# Wiznet.net
KiCad netlist of a schematic drawn in Altium Designer
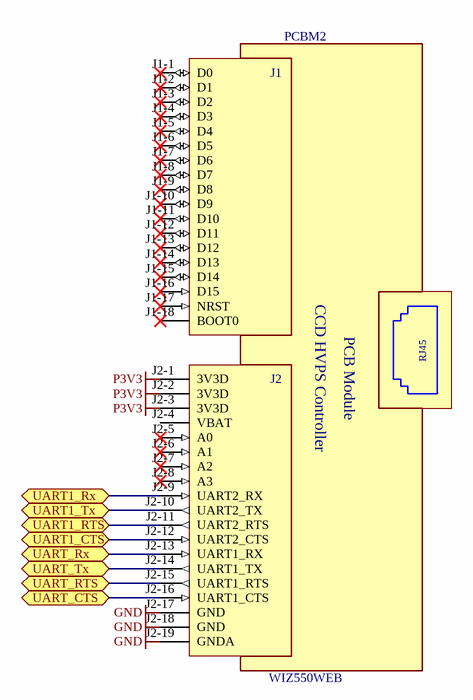
[diagram p0: Wiznet.SchDoc]

(export (version "E")
  (design (tool "Eeschema 10.0.6"))
  (components
    (comp (ref "PCBM2")
      (value "WIZ550WEB")
      (footprint "PCBM_WIZNET_WIZ550WEB")
      (description "Embedded Web Server Module base on W5500 TCP/IP Chip")
      (fields
        (field (name "PART NUMBER") "PCBM_WIZNET_WIZ550WEB")
        (field (name "MANUFACTURER") "WIZNET")
        (field (name "AUTHOR") "CERN DEM MR")
      )
      (libsource (lib "ICs And Semiconductors") (part "PCBM_WIZNET_WIZ550WEB"))
    )
  )
  (nets
    (net (code "1") (name "/UART1_CTS") (class "Default")
      (node (ref "PCBM2") (pin "J2-12") (pinfunction "UART2_CTS_J2-12") (pintype "input"))
    )
    (net (code "2") (name "/UART1_RTS") (class "Default")
      (node (ref "PCBM2") (pin "J2-11") (pinfunction "UART2_RTS_J2-11") (pintype "output"))
    )
    (net (code "3") (name "/UART1_Rx") (class "Default")
      (node (ref "PCBM2") (pin "J2-9") (pinfunction "UART2_RX_J2-9") (pintype "input"))
    )
    (net (code "4") (name "/UART1_Tx") (class "Default")
      (node (ref "PCBM2") (pin "J2-10") (pinfunction "UART2_TX_J2-10") (pintype "output"))
    )
    (net (code "5") (name "/UART_CTS") (class "Default")
      (node (ref "PCBM2") (pin "J2-16") (pinfunction "UART1_CTS_J2-16") (pintype "input"))
    )
    (net (code "6") (name "/UART_RTS") (class "Default")
      (node (ref "PCBM2") (pin "J2-15") (pinfunction "UART1_RTS_J2-15") (pintype "output"))
    )
    (net (code "7") (name "/UART_Rx") (class "Default")
      (node (ref "PCBM2") (pin "J2-13") (pinfunction "UART1_RX_J2-13") (pintype "input"))
    )
    (net (code "8") (name "/UART_Tx") (class "Default")
      (node (ref "PCBM2") (pin "J2-14") (pinfunction "UART1_TX_J2-14") (pintype "output"))
    )
    (net (code "9") (name "GND") (class "Default")
      (node (ref "PCBM2") (pin "J2-17") (pinfunction "GND_J2-17") (pintype "power_in"))
      (node (ref "PCBM2") (pin "J2-18") (pinfunction "GND_J2-18") (pintype "power_in"))
      (node (ref "PCBM2") (pin "J2-19") (pinfunction "GNDA_J2-19") (pintype "power_in"))
    )
    (net (code "10") (name "P3V3") (class "Default")
      (node (ref "PCBM2") (pin "J2-1") (pinfunction "3V3D_J2-1") (pintype "power_in"))
      (node (ref "PCBM2") (pin "J2-2") (pinfunction "3V3D_J2-2") (pintype "power_in"))
      (node (ref "PCBM2") (pin "J2-3") (pinfunction "3V3D_J2-3") (pintype "power_in"))
    )
    (net (code "11") (name "unconnected-(PCBM2-A0-PadJ2-5)") (class "Default")
      (node (ref "PCBM2") (pin "J2-5") (pinfunction "A0_J2-5") (pintype "input+no_connect"))
    )
    (net (code "12") (name "unconnected-(PCBM2-A1-PadJ2-6)") (class "Default")
      (node (ref "PCBM2") (pin "J2-6") (pinfunction "A1_J2-6") (pintype "input+no_connect"))
    )
    (net (code "13") (name "unconnected-(PCBM2-A2-PadJ2-7)") (class "Default")
      (node (ref "PCBM2") (pin "J2-7") (pinfunction "A2_J2-7") (pintype "input+no_connect"))
    )
    (net (code "14") (name "unconnected-(PCBM2-A3-PadJ2-8)") (class "Default")
      (node (ref "PCBM2") (pin "J2-8") (pinfunction "A3_J2-8") (pintype "input+no_connect"))
    )
    (net (code "15") (name "unconnected-(PCBM2-BOOT0-PadJ1-18)") (class "Default")
      (node (ref "PCBM2") (pin "J1-18") (pinfunction "BOOT0_J1-18") (pintype "power_in+no_connect"))
    )
    (net (code "16") (name "unconnected-(PCBM2-D0-PadJ1-1)") (class "Default")
      (node (ref "PCBM2") (pin "J1-1") (pinfunction "D0_J1-1") (pintype "bidirectional+no_connect"))
    )
    (net (code "17") (name "unconnected-(PCBM2-D1-PadJ1-2)") (class "Default")
      (node (ref "PCBM2") (pin "J1-2") (pinfunction "D1_J1-2") (pintype "bidirectional+no_connect"))
    )
    (net (code "18") (name "unconnected-(PCBM2-D2-PadJ1-3)") (class "Default")
      (node (ref "PCBM2") (pin "J1-3") (pinfunction "D2_J1-3") (pintype "bidirectional+no_connect"))
    )
    (net (code "19") (name "unconnected-(PCBM2-D3-PadJ1-4)") (class "Default")
      (node (ref "PCBM2") (pin "J1-4") (pinfunction "D3_J1-4") (pintype "bidirectional+no_connect"))
    )
    (net (code "20") (name "unconnected-(PCBM2-D4-PadJ1-5)") (class "Default")
      (node (ref "PCBM2") (pin "J1-5") (pinfunction "D4_J1-5") (pintype "bidirectional+no_connect"))
    )
    (net (code "21") (name "unconnected-(PCBM2-D5-PadJ1-6)") (class "Default")
      (node (ref "PCBM2") (pin "J1-6") (pinfunction "D5_J1-6") (pintype "bidirectional+no_connect"))
    )
    (net (code "22") (name "unconnected-(PCBM2-D6-PadJ1-7)") (class "Default")
      (node (ref "PCBM2") (pin "J1-7") (pinfunction "D6_J1-7") (pintype "bidirectional+no_connect"))
    )
    (net (code "23") (name "unconnected-(PCBM2-D7-PadJ1-8)") (class "Default")
      (node (ref "PCBM2") (pin "J1-8") (pinfunction "D7_J1-8") (pintype "bidirectional+no_connect"))
    )
    (net (code "24") (name "unconnected-(PCBM2-D8-PadJ1-9)") (class "Default")
      (node (ref "PCBM2") (pin "J1-9") (pinfunction "D8_J1-9") (pintype "bidirectional+no_connect"))
    )
    (net (code "25") (name "unconnected-(PCBM2-D9-PadJ1-10)") (class "Default")
      (node (ref "PCBM2") (pin "J1-10") (pinfunction "D9_J1-10") (pintype "bidirectional+no_connect"))
    )
    (net (code "26") (name "unconnected-(PCBM2-D10-PadJ1-11)") (class "Default")
      (node (ref "PCBM2") (pin "J1-11") (pinfunction "D10_J1-11") (pintype "bidirectional+no_connect"))
    )
    (net (code "27") (name "unconnected-(PCBM2-D11-PadJ1-12)") (class "Default")
      (node (ref "PCBM2") (pin "J1-12") (pinfunction "D11_J1-12") (pintype "bidirectional+no_connect"))
    )
    (net (code "28") (name "unconnected-(PCBM2-D12-PadJ1-13)") (class "Default")
      (node (ref "PCBM2") (pin "J1-13") (pinfunction "D12_J1-13") (pintype "bidirectional+no_connect"))
    )
    (net (code "29") (name "unconnected-(PCBM2-D13-PadJ1-14)") (class "Default")
      (node (ref "PCBM2") (pin "J1-14") (pinfunction "D13_J1-14") (pintype "bidirectional+no_connect"))
    )
    (net (code "30") (name "unconnected-(PCBM2-D14-PadJ1-15)") (class "Default")
      (node (ref "PCBM2") (pin "J1-15") (pinfunction "D14_J1-15") (pintype "bidirectional+no_connect"))
    )
    (net (code "31") (name "unconnected-(PCBM2-D15-PadJ1-16)") (class "Default")
      (node (ref "PCBM2") (pin "J1-16") (pinfunction "D15_J1-16") (pintype "input+no_connect"))
    )
    (net (code "32") (name "unconnected-(PCBM2-NRST-PadJ1-17)") (class "Default")
      (node (ref "PCBM2") (pin "J1-17") (pinfunction "NRST_J1-17") (pintype "input+no_connect"))
    )
    (net (code "33") (name "unconnected-(PCBM2-VBAT-PadJ2-4)") (class "Default")
      (node (ref "PCBM2") (pin "J2-4") (pinfunction "VBAT_J2-4") (pintype "power_in"))
    )
  )
)
